# 2_-_5V_Buck.net
KiCad netlist of a schematic drawn in Altium Designer
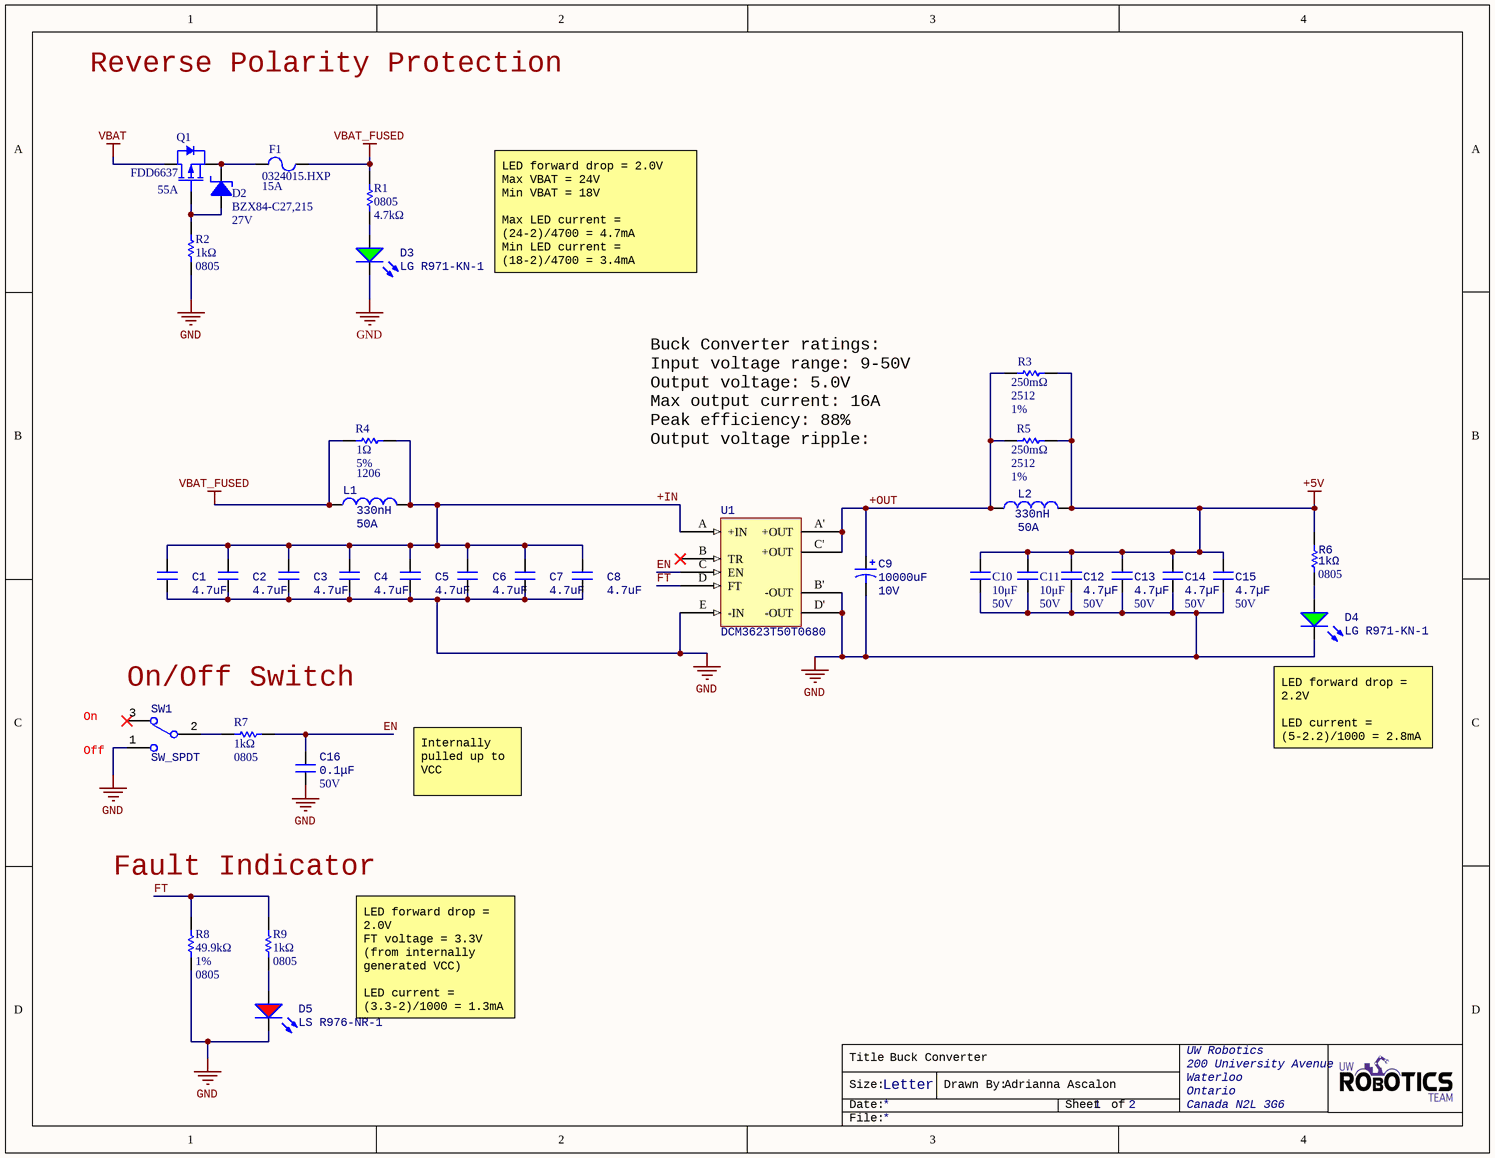
[diagram p0: 2 - 5V Buck.SchDoc]

(export (version "E")
  (design (tool "Eeschema 10.0.6"))
  (components
    (comp (ref "C1")
      (value "4.7uF")
      (footprint "CAPC5750X7R2A")
      (description "CAP CER 4.7UF 100V X7R 2220")
      (fields
        (field (name "MANUFACTURER") "TDK")
        (field (name "MANUFACTURER PART NUMBER") "C5750X7R2A475M230KA")
      )
      (libsource (lib "UWRT_Schematic_Library_2020") (part "CAP_4.7uF_100V_2220"))
    )
    (comp (ref "C2")
      (value "4.7uF")
      (footprint "CAPC5750X7R2A")
      (description "CAP CER 4.7UF 100V X7R 2220")
      (fields
        (field (name "MANUFACTURER") "TDK")
        (field (name "MANUFACTURER PART NUMBER") "C5750X7R2A475M230KA")
      )
      (libsource (lib "UWRT_Schematic_Library_2020") (part "CAP_4.7uF_100V_2220"))
    )
    (comp (ref "C3")
      (value "4.7uF")
      (footprint "CAPC5750X7R2A")
      (description "CAP CER 4.7UF 100V X7R 2220")
      (fields
        (field (name "MANUFACTURER") "TDK")
        (field (name "MANUFACTURER PART NUMBER") "C5750X7R2A475M230KA")
      )
      (libsource (lib "UWRT_Schematic_Library_2020") (part "CAP_4.7uF_100V_2220"))
    )
    (comp (ref "C4")
      (value "4.7uF")
      (footprint "CAPC5750X7R2A")
      (description "CAP CER 4.7UF 100V X7R 2220")
      (fields
        (field (name "MANUFACTURER") "TDK")
        (field (name "MANUFACTURER PART NUMBER") "C5750X7R2A475M230KA")
      )
      (libsource (lib "UWRT_Schematic_Library_2020") (part "CAP_4.7uF_100V_2220"))
    )
    (comp (ref "C5")
      (value "4.7uF")
      (footprint "CAPC5750X7R2A")
      (description "CAP CER 4.7UF 100V X7R 2220")
      (fields
        (field (name "MANUFACTURER") "TDK")
        (field (name "MANUFACTURER PART NUMBER") "C5750X7R2A475M230KA")
      )
      (libsource (lib "UWRT_Schematic_Library_2020") (part "CAP_4.7uF_100V_2220"))
    )
    (comp (ref "C6")
      (value "4.7uF")
      (footprint "CAPC5750X7R2A")
      (description "CAP CER 4.7UF 100V X7R 2220")
      (fields
        (field (name "MANUFACTURER") "TDK")
        (field (name "MANUFACTURER PART NUMBER") "C5750X7R2A475M230KA")
      )
      (libsource (lib "UWRT_Schematic_Library_2020") (part "CAP_4.7uF_100V_2220"))
    )
    (comp (ref "C7")
      (value "4.7uF")
      (footprint "CAPC5750X7R2A")
      (description "CAP CER 4.7UF 100V X7R 2220")
      (fields
        (field (name "MANUFACTURER") "TDK")
        (field (name "MANUFACTURER PART NUMBER") "C5750X7R2A475M230KA")
      )
      (libsource (lib "UWRT_Schematic_Library_2020") (part "CAP_4.7uF_100V_2220"))
    )
    (comp (ref "C8")
      (value "4.7uF")
      (footprint "CAPC5750X7R2A")
      (description "CAP CER 4.7UF 100V X7R 2220")
      (fields
        (field (name "MANUFACTURER") "TDK")
        (field (name "MANUFACTURER PART NUMBER") "C5750X7R2A475M230KA")
      )
      (libsource (lib "UWRT_Schematic_Library_2020") (part "CAP_4.7uF_100V_2220"))
    )
    (comp (ref "C9")
      (value "URS1A103MHD1TN")
      (footprint "CAP_UBY_18X25_NC")
      (description "CAP ALUM 10000UF 20% 10V RADIAL")
      (fields
        (field (name "TOLERANCE") "20%")
        (field (name "CAPACITANCE") "10000uF")
        (field (name "VOLTAGE RATING") "10V")
      )
      (libsource (lib "UWRT_Schematic_Library_2020") (part "URS1A103MHD1TN"))
    )
    (comp (ref "C10")
      (value "10μF")
      (footprint "CAPC1206(3216)")
      (description "CAP CER 10UF 50V X5R 1206")
      (fields (field (name "VOLTAGE RATING") "50V") (field (name "Comment") "10uF"))
      (libsource (lib "UWRT_Schematic_Library_2020") (part "CAP_10uF_50V_1206"))
    )
    (comp (ref "C11")
      (value "10μF")
      (footprint "CAPC1206(3216)")
      (description "CAP CER 10UF 50V X5R 1206")
      (fields (field (name "VOLTAGE RATING") "50V") (field (name "Comment") "10uF"))
      (libsource (lib "UWRT_Schematic_Library_2020") (part "CAP_10uF_50V_1206"))
    )
    (comp (ref "C12")
      (value "4.7µF")
      (footprint "UWRT_Footprint_Library_2020:CAPC1206(3216)")
      (description "CAP CER 4.7UF 50V X7R 1206")
      (fields (field (name "TOLERANCE") "10%") (field (name "VOLTAGE") "50V"))
      (libsource (lib "UWRT_Schematic_Library_2020") (part "CAP_4.7µF_50V_1206"))
    )
    (comp (ref "C13")
      (value "4.7µF")
      (footprint "UWRT_Footprint_Library_2020:CAPC1206(3216)")
      (description "CAP CER 4.7UF 50V X7R 1206")
      (fields (field (name "TOLERANCE") "10%") (field (name "VOLTAGE") "50V"))
      (libsource (lib "UWRT_Schematic_Library_2020") (part "CAP_4.7µF_50V_1206"))
    )
    (comp (ref "C14")
      (value "4.7µF")
      (footprint "UWRT_Footprint_Library_2020:CAPC1206(3216)")
      (description "CAP CER 4.7UF 50V X7R 1206")
      (fields (field (name "TOLERANCE") "10%") (field (name "VOLTAGE") "50V"))
      (libsource (lib "UWRT_Schematic_Library_2020") (part "CAP_4.7µF_50V_1206"))
    )
    (comp (ref "C15")
      (value "4.7µF")
      (footprint "UWRT_Footprint_Library_2020:CAPC1206(3216)")
      (description "CAP CER 4.7UF 50V X7R 1206")
      (fields (field (name "TOLERANCE") "10%") (field (name "VOLTAGE") "50V"))
      (libsource (lib "UWRT_Schematic_Library_2020") (part "CAP_4.7µF_50V_1206"))
    )
    (comp (ref "C16")
      (value "0.1μF")
      (footprint "CAPC2012X140N")
      (description "CAP CER 0.1UF 50V X7R 0805")
      (fields (field (name "VOLTAGE RATING") "50V") (field (name "TOLERANCE") "10%"))
      (libsource (lib "UWRT_Schematic_Library_2020") (part "CAP_0.1uF_50V_0805"))
    )
    (comp (ref "D2")
      (value "DIO_ZENER_27V")
      (footprint "SOT23-3")
      (description "DIODE ZENER 27V 250MW SOT23")
      (fields
        (field (name "MANUFACTURER PART NUMBER 1") "BZX84-C27,215")
        (field (name "TOLERANCE") "5%")
        (field (name "WORKING VOLTAGE") "27V")
      )
      (libsource (lib "UWRT_Schematic_Library_2020") (part "DIO_ZENER_27V"))
    )
    (comp (ref "D3")
      (value "LG R971-KN-1")
      (footprint "LED_0805_LINE")
      (description "LED GREEN DIFFUSED 0805 SMD")
      (libsource (lib "UWRT_Schematic_Library_2020") (part "DIO_LED_G"))
    )
    (comp (ref "D4")
      (value "LG R971-KN-1")
      (footprint "LED_0805_LINE")
      (description "LED GREEN DIFFUSED 0805 SMD")
      (libsource (lib "UWRT_Schematic_Library_2020") (part "DIO_LED_G"))
    )
    (comp (ref "D5")
      (value "LS R976-NR-1")
      (footprint "LED_0805_LINE")
      (description "LED RED DIFFUSED 0805 SMD")
      (libsource (lib "UWRT_Schematic_Library_2020") (part "DIO_LED_R"))
    )
    (comp (ref "F1")
      (value "0324015.HXP")
      (footprint "FUSE")
      (description "FUSE CERM 15A 250VAC 125VDC 3AB")
      (fields (field (name "CURRENT RATING") "15A"))
      (libsource (lib "UWRT_Schematic_Library_2020") (part "0324015.HXP"))
    )
    (comp (ref "L1")
      (value "744309033")
      (footprint "WE-HCM 1390")
      (description "Wurth Shielded Wire-wound SMD Inductor with a MnZn Core, 0.33 µH ±20% Flat Wire Winding 47.5A Idc")
      (fields
        (field (name "TOLERANCE") "20%")
        (field (name "MAX DC CURRENT") "50A")
        (field (name "INDUCTANCE") "330nH")
      )
      (libsource (lib "UWRT_Schematic_Library_2020") (part "744309033"))
    )
    (comp (ref "L2")
      (value "744309033")
      (footprint "WE-HCM 1390")
      (description "Wurth Shielded Wire-wound SMD Inductor with a MnZn Core, 0.33 µH ±20% Flat Wire Winding 47.5A Idc")
      (fields
        (field (name "TOLERANCE") "20%")
        (field (name "MAX DC CURRENT") "50A")
        (field (name "INDUCTANCE") "330nH")
      )
      (libsource (lib "UWRT_Schematic_Library_2020") (part "744309033"))
    )
    (comp (ref "Q1")
      (value "FDD6637")
      (footprint "UWRT_Footprint_Library_2020:D-PAK")
      (description "Trans MOSFET P-CH 35V 13A 3-Pin(2+Tab) DPAK T/R")
      (fields
        (field (name "MANUFACTURER PART NUMBER 1") "FDD6637")
        (field (name "CONTINUOUS DRAIN CURRENT (ID)") "55A")
      )
      (libsource (lib "UWRT_Schematic_Library_2020") (part "FDD6637"))
    )
    (comp (ref "R1")
      (value "4.7kΩ")
      (footprint "RESC2012X60N")
      (description "RES SMD 4.7K OHM 5% 1/8W 0805")
      (fields
        (field (name "TOLERANCE") "5%")
        (field (name "CASE CODE (IMPERIAL)") "0805")
        (field (name "Comment") "RES_4.7kΩ_0805")
      )
      (libsource (lib "UWRT_Schematic_Library_2020") (part "RES_4.7kΩ_0805"))
    )
    (comp (ref "R2")
      (value "1kΩ")
      (footprint "RESC2012X60N")
      (description "RES SMD 1K OHM 1% 1/8W 0805")
      (fields (field (name "TOLERANCE") "1%") (field (name "CASE CODE (IMPERIAL)") "0805"))
      (libsource (lib "UWRT_Schematic_Library_2020") (part "RES_1kΩ_0805"))
    )
    (comp (ref "R3")
      (value "WSL2512R2500FEA")
      (footprint "RESC6432X89X76NL25T25")
      (description "Chip Resistor, 250 mOhm, +/- 1%, 1 W, -65 to 170 degC, 2512 (6432 Metric), RoHS, Tape and Reel")
      (fields
        (field (name "MANUFACTURER") "Vishay")
        (field (name "PACKAGE REFERENCE") "2512")
        (field (name "RESISTANCE TOLERANCE") "1%")
        (field (name "RESISTANCE") "250mΩ")
      )
      (libsource (lib "UWRT_Schematic_Library_2020") (part "RES_250mΩ_2512"))
    )
    (comp (ref "R4")
      (value "RES_1Ω_1206")
      (footprint "RESC1206(3216)_N")
      (description "RES 1 OHM 5% 1/4W 1206")
      (fields
        (field (name "MANUFACTURER") "KOA Speer")
        (field (name "MANUFACTURER PART NUMBER") "RK73B2BTTE1R0J")
        (field (name "TOLERANCE") "5%")
        (field (name "CASE CODE (IMPERIAL)") "1206")
        (field (name "RESISTANCE") "1Ω")
      )
      (libsource (lib "UWRT_Schematic_Library_2020") (part "RES_1Ω_1206"))
    )
    (comp (ref "R5")
      (value "WSL2512R2500FEA")
      (footprint "RESC6432X89X76NL25T25")
      (description "Chip Resistor, 250 mOhm, +/- 1%, 1 W, -65 to 170 degC, 2512 (6432 Metric), RoHS, Tape and Reel")
      (fields
        (field (name "MANUFACTURER") "Vishay")
        (field (name "PACKAGE REFERENCE") "2512")
        (field (name "RESISTANCE TOLERANCE") "1%")
        (field (name "RESISTANCE") "250mΩ")
      )
      (libsource (lib "UWRT_Schematic_Library_2020") (part "RES_250mΩ_2512"))
    )
    (comp (ref "R6")
      (value "1kΩ")
      (footprint "RESC2012X60N")
      (description "RES SMD 1K OHM 1% 1/8W 0805")
      (fields (field (name "TOLERANCE") "1%") (field (name "CASE CODE (IMPERIAL)") "0805"))
      (libsource (lib "UWRT_Schematic_Library_2020") (part "RES_1kΩ_0805"))
    )
    (comp (ref "R7")
      (value "1kΩ")
      (footprint "RESC2012X60N")
      (description "RES SMD 1K OHM 1% 1/8W 0805")
      (fields (field (name "TOLERANCE") "1%") (field (name "CASE CODE (IMPERIAL)") "0805"))
      (libsource (lib "UWRT_Schematic_Library_2020") (part "RES_1kΩ_0805"))
    )
    (comp (ref "R8")
      (value "49.9kΩ")
      (footprint "RESC2012X60N")
      (description "RES SMD 49.9K OHM 1% 1/8W 0805")
      (fields (field (name "TOLERANCE") "1%") (field (name "CASE CODE (IMPERIAL)") "0805"))
      (libsource (lib "UWRT_Schematic_Library_2020") (part "RES_49.9kΩ_0805"))
    )
    (comp (ref "R9")
      (value "1kΩ")
      (footprint "RESC2012X60N")
      (description "RES SMD 1K OHM 1% 1/8W 0805")
      (fields (field (name "TOLERANCE") "1%") (field (name "CASE CODE (IMPERIAL)") "0805"))
      (libsource (lib "UWRT_Schematic_Library_2020") (part "RES_1kΩ_0805"))
    )
    (comp (ref "SW1")
      (value "SW_SPDT")
      (footprint "100SP1T1B4M2QE")
      (description "SWITCH TOGGLE SPDT 5A 120V")
      (libsource (lib "UWRT_Schematic_Library_2020") (part "SW_SPDT"))
    )
    (comp (ref "U1")
      (value "DCM3623T50T0680")
      (footprint "DCM3623T50T0680")
      (libsource (lib "UWRT_Schematic_Library_2020") (part "DCM3623T50T0680"))
    )
  )
  (nets
    (net (code "1") (name "+5V") (class "Default")
      (node (ref "C10") (pin "2") (pinfunction "2_2") (pintype "passive"))
      (node (ref "C11") (pin "2") (pinfunction "2_2") (pintype "passive"))
      (node (ref "C12") (pin "2") (pinfunction "2_2") (pintype "passive"))
      (node (ref "C13") (pin "2") (pinfunction "2_2") (pintype "passive"))
      (node (ref "C14") (pin "2") (pinfunction "2_2") (pintype "passive"))
      (node (ref "C15") (pin "2") (pinfunction "2_2") (pintype "passive"))
      (node (ref "L2") (pin "2") (pinfunction "2_2") (pintype "passive"))
      (node (ref "R3") (pin "2") (pinfunction "2_2") (pintype "passive"))
      (node (ref "R5") (pin "2") (pinfunction "2_2") (pintype "passive"))
      (node (ref "R6") (pin "2") (pinfunction "2_2") (pintype "passive"))
    )
    (net (code "2") (name "/+IN") (class "Default")
      (node (ref "C1") (pin "2") (pinfunction "2_2") (pintype "passive"))
      (node (ref "C2") (pin "2") (pinfunction "2_2") (pintype "passive"))
      (node (ref "C3") (pin "2") (pinfunction "2_2") (pintype "passive"))
      (node (ref "C4") (pin "2") (pinfunction "2_2") (pintype "passive"))
      (node (ref "C5") (pin "2") (pinfunction "2_2") (pintype "passive"))
      (node (ref "C6") (pin "2") (pinfunction "2_2") (pintype "passive"))
      (node (ref "C7") (pin "2") (pinfunction "2_2") (pintype "passive"))
      (node (ref "C8") (pin "2") (pinfunction "2_2") (pintype "passive"))
      (node (ref "L1") (pin "2") (pinfunction "2_2") (pintype "passive"))
      (node (ref "R4") (pin "2") (pinfunction "2_2") (pintype "passive"))
      (node (ref "U1") (pin "A") (pinfunction "+IN_A") (pintype "input"))
    )
    (net (code "3") (name "/+OUT") (class "Default")
      (node (ref "C9") (pin "1") (pinfunction "1_1") (pintype "passive"))
      (node (ref "L2") (pin "1") (pinfunction "1_1") (pintype "passive"))
      (node (ref "R3") (pin "1") (pinfunction "1_1") (pintype "passive"))
      (node (ref "R5") (pin "1") (pinfunction "1_1") (pintype "passive"))
      (node (ref "U1") (pin "A'") (pinfunction "+OUT_A'") (pintype "passive"))
      (node (ref "U1") (pin "C'") (pinfunction "+OUT_C'") (pintype "passive"))
    )
    (net (code "4") (name "/EN") (class "Default")
      (node (ref "C16") (pin "2") (pinfunction "2_2") (pintype "passive"))
      (node (ref "R7") (pin "2") (pinfunction "2_2") (pintype "passive"))
      (node (ref "U1") (pin "C") (pinfunction "EN_C") (pintype "input"))
    )
    (net (code "5") (name "/FT") (class "Default")
      (node (ref "R8") (pin "1") (pinfunction "1_1") (pintype "passive"))
      (node (ref "R9") (pin "2") (pinfunction "2_2") (pintype "passive"))
      (node (ref "U1") (pin "D") (pinfunction "FT_D") (pintype "input"))
    )
    (net (code "6") (name "GND") (class "Default")
      (node (ref "C1") (pin "1") (pinfunction "1_1") (pintype "passive"))
      (node (ref "C10") (pin "1") (pinfunction "1_1") (pintype "passive"))
      (node (ref "C11") (pin "1") (pinfunction "1_1") (pintype "passive"))
      (node (ref "C12") (pin "1") (pinfunction "1_1") (pintype "passive"))
      (node (ref "C13") (pin "1") (pinfunction "1_1") (pintype "passive"))
      (node (ref "C14") (pin "1") (pinfunction "1_1") (pintype "passive"))
      (node (ref "C15") (pin "1") (pinfunction "1_1") (pintype "passive"))
      (node (ref "C16") (pin "1") (pinfunction "1_1") (pintype "passive"))
      (node (ref "C2") (pin "1") (pinfunction "1_1") (pintype "passive"))
      (node (ref "C3") (pin "1") (pinfunction "1_1") (pintype "passive"))
      (node (ref "C4") (pin "1") (pinfunction "1_1") (pintype "passive"))
      (node (ref "C5") (pin "1") (pinfunction "1_1") (pintype "passive"))
      (node (ref "C6") (pin "1") (pinfunction "1_1") (pintype "passive"))
      (node (ref "C7") (pin "1") (pinfunction "1_1") (pintype "passive"))
      (node (ref "C8") (pin "1") (pinfunction "1_1") (pintype "passive"))
      (node (ref "C9") (pin "2") (pinfunction "2_2") (pintype "passive"))
      (node (ref "D3") (pin "2") (pinfunction "K_2") (pintype "passive"))
      (node (ref "D4") (pin "2") (pinfunction "K_2") (pintype "passive"))
      (node (ref "D5") (pin "2") (pinfunction "K_2") (pintype "passive"))
      (node (ref "R2") (pin "1") (pinfunction "1_1") (pintype "passive"))
      (node (ref "R8") (pin "2") (pinfunction "2_2") (pintype "passive"))
      (node (ref "SW1") (pin "1") (pinfunction "1_1") (pintype "passive"))
      (node (ref "U1") (pin "B'") (pinfunction "-OUT_B'") (pintype "passive"))
      (node (ref "U1") (pin "D'") (pinfunction "-OUT_D'") (pintype "passive"))
      (node (ref "U1") (pin "E") (pinfunction "-IN_E") (pintype "input"))
    )
    (net (code "7") (name "Net-(D2-Anode)") (class "Default")
      (node (ref "D2") (pin "1") (pinfunction "Anode_1") (pintype "passive"))
      (node (ref "Q1") (pin "1") (pinfunction "Gate_1") (pintype "passive"))
      (node (ref "R2") (pin "2") (pinfunction "2_2") (pintype "passive"))
    )
    (net (code "8") (name "Net-(D2-Cathode)") (class "Default")
      (node (ref "D2") (pin "2") (pinfunction "Cathode_2") (pintype "passive"))
      (node (ref "F1") (pin "1") (pinfunction "1_1") (pintype "passive"))
      (node (ref "Q1") (pin "3") (pinfunction "Source_3") (pintype "passive"))
    )
    (net (code "9") (name "Net-(D3-A)") (class "Default")
      (node (ref "D3") (pin "1") (pinfunction "A_1") (pintype "passive"))
      (node (ref "R1") (pin "1") (pinfunction "1_1") (pintype "passive"))
    )
    (net (code "10") (name "Net-(D4-A)") (class "Default")
      (node (ref "D4") (pin "1") (pinfunction "A_1") (pintype "passive"))
      (node (ref "R6") (pin "1") (pinfunction "1_1") (pintype "passive"))
    )
    (net (code "11") (name "Net-(D5-A)") (class "Default")
      (node (ref "D5") (pin "1") (pinfunction "A_1") (pintype "passive"))
      (node (ref "R9") (pin "1") (pinfunction "1_1") (pintype "passive"))
    )
    (net (code "12") (name "Net-(R7-Pad1)") (class "Default")
      (node (ref "R7") (pin "1") (pinfunction "1_1") (pintype "passive"))
      (node (ref "SW1") (pin "2") (pinfunction "2_2") (pintype "passive"))
    )
    (net (code "13") (name "VBAT") (class "Default")
      (node (ref "Q1") (pin "2") (pinfunction "Drain_2") (pintype "passive"))
    )
    (net (code "14") (name "VBAT_FUSED") (class "Default")
      (node (ref "F1") (pin "2") (pinfunction "2_2") (pintype "passive"))
      (node (ref "L1") (pin "1") (pinfunction "1_1") (pintype "passive"))
      (node (ref "R1") (pin "2") (pinfunction "2_2") (pintype "passive"))
      (node (ref "R4") (pin "1") (pinfunction "1_1") (pintype "passive"))
    )
    (net (code "15") (name "unconnected-(SW1-Pad3)") (class "Default")
      (node (ref "SW1") (pin "3") (pinfunction "3_3") (pintype "passive+no_connect"))
    )
    (net (code "16") (name "unconnected-(U1-TR-PadB)") (class "Default")
      (node (ref "U1") (pin "B") (pinfunction "TR_B") (pintype "input+no_connect"))
    )
  )
)
